# Board_AWS_ESP32_v6.net
KiCad netlist of a schematic drawn in EAGLE
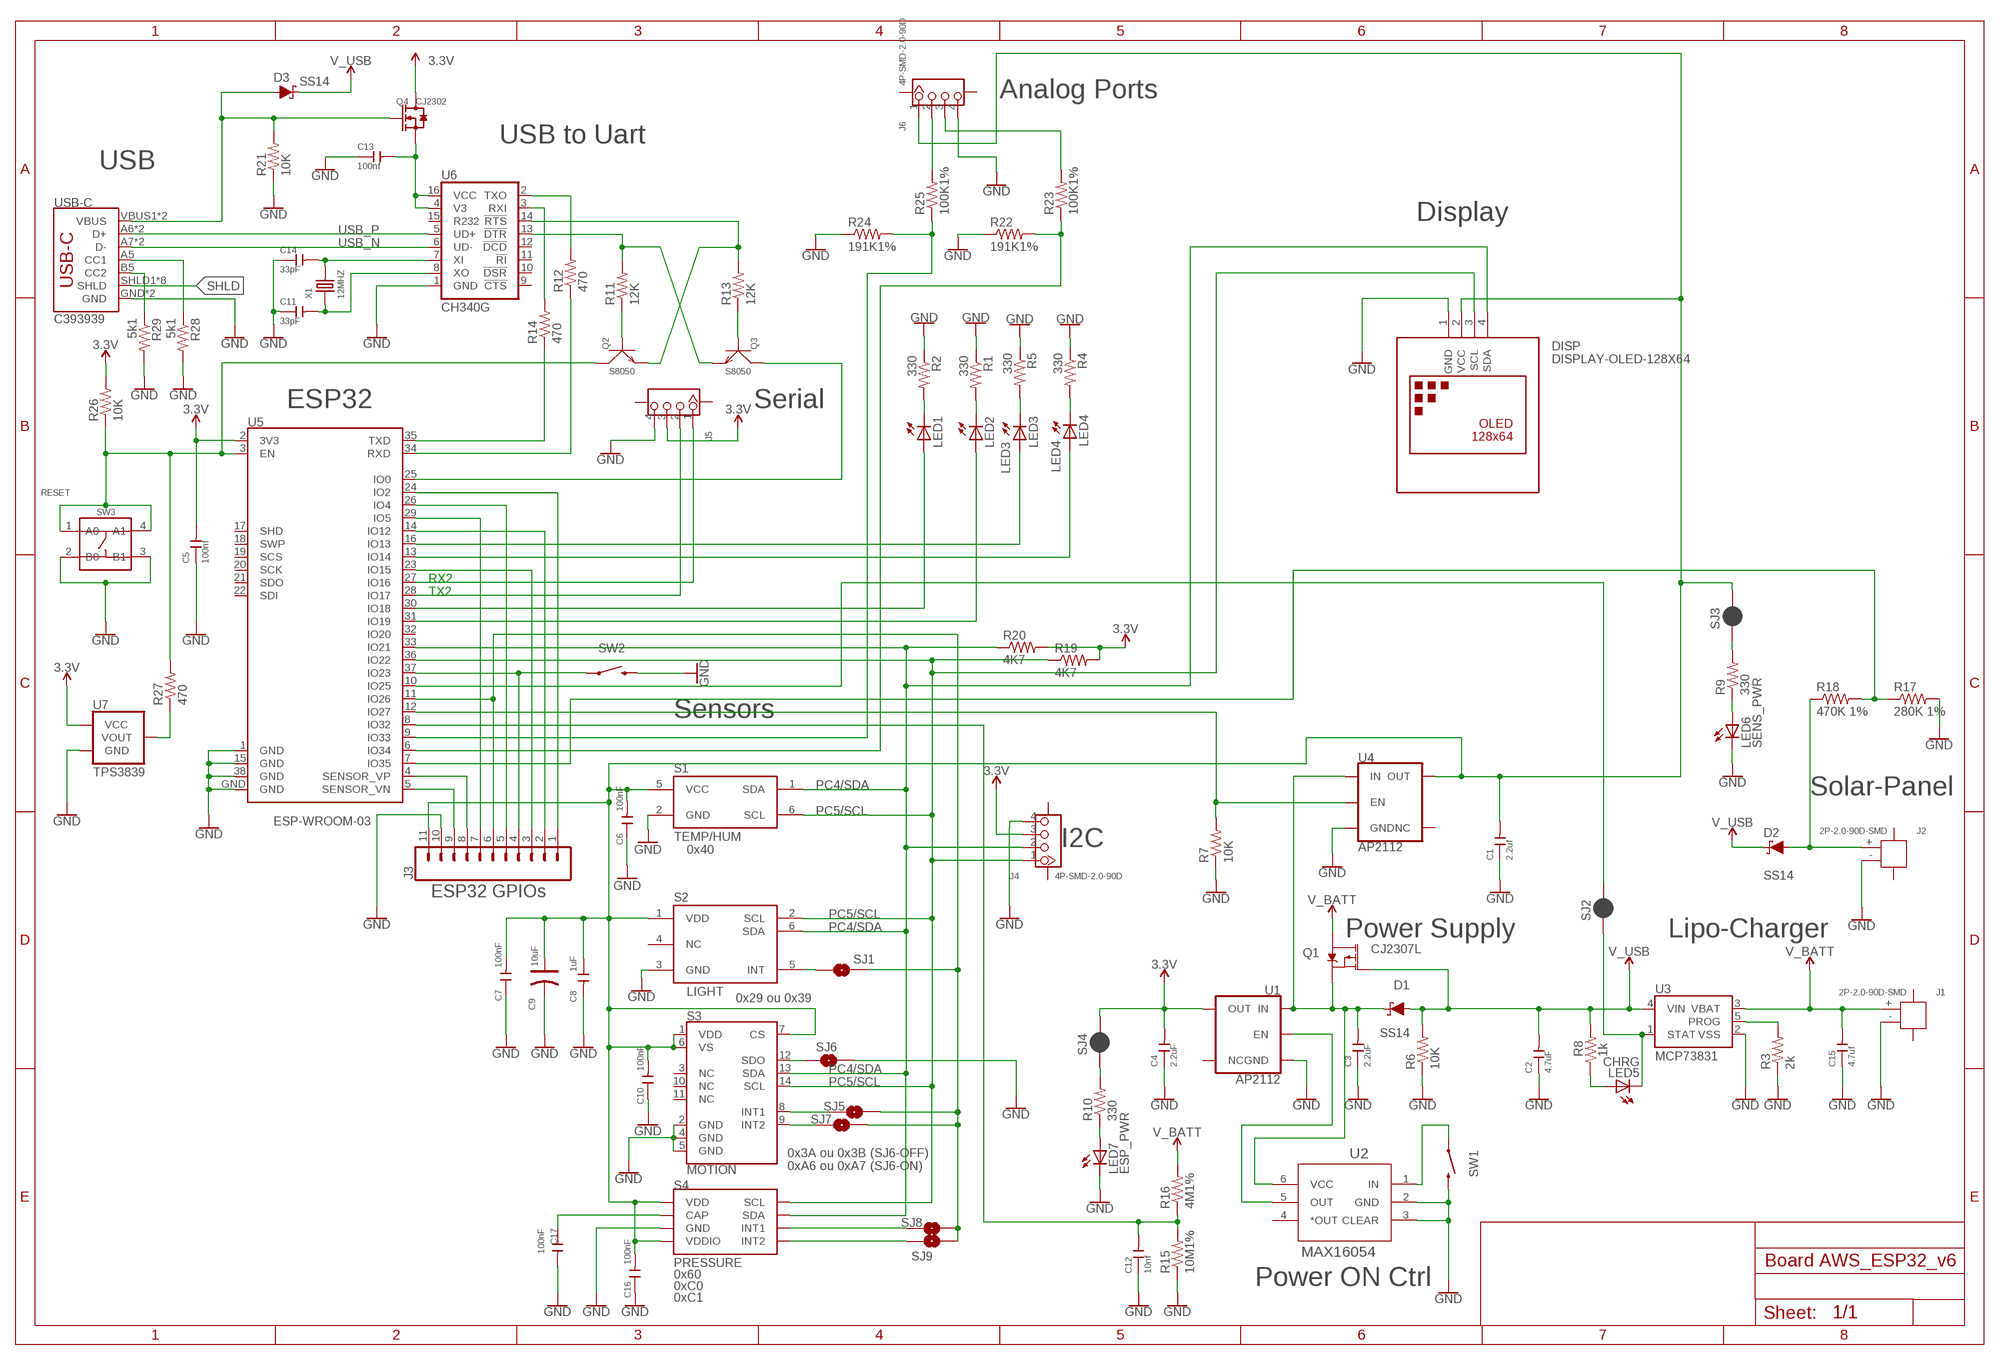
[diagram p0: schematic, sheet 1]

(export (version "E")
  (design (tool "Eeschema 10.0.6"))
  (components
    (comp (ref "C1")
      (value "2.2uf")
      (footprint "eagle-import:C0603")
      (fields (field (name "MPN") "CC0603KRX7R6BB225"))
      (libsource (lib "eagle-import") (part "CERAMIC-2.2UF-10V-10%-X7R(0603)"))
    )
    (comp (ref "C2")
      (value "4.7uF")
      (footprint "eagle-import:C0603")
      (fields (field (name "MPN") "CC0603KRX5R6BB475"))
      (libsource (lib "eagle-import") (part "CERAMIC-4.7UF-10V-10%-X5R(0603)"))
    )
    (comp (ref "C3")
      (value "2.2uF")
      (footprint "eagle-import:C0603")
      (fields (field (name "MPN") "CC0603KRX7R6BB225"))
      (libsource (lib "eagle-import") (part "CERAMIC-2.2UF-10V-10%-X7R(0603)"))
    )
    (comp (ref "C4")
      (value "2.2uF")
      (footprint "eagle-import:C0603")
      (fields (field (name "MPN") "CC0603KRX7R6BB225"))
      (libsource (lib "eagle-import") (part "CERAMIC-2.2UF-10V-10%-X7R(0603)"))
    )
    (comp (ref "C5")
      (value "100nf")
      (footprint "eagle-import:C0603")
      (fields (field (name "MPN") "CC0603KRX7R9BB104"))
      (libsource (lib "eagle-import") (part "CERAMIC-100NF-50V-10%-X7R(0603)"))
    )
    (comp (ref "C6")
      (value "100nF")
      (footprint "eagle-import:C0603")
      (libsource (lib "eagle-import") (part "C-0603"))
    )
    (comp (ref "C7")
      (value "100nF")
      (footprint "eagle-import:C0603")
      (libsource (lib "eagle-import") (part "C-0603"))
    )
    (comp (ref "C8")
      (value "1uF")
      (footprint "eagle-import:C0805")
      (libsource (lib "eagle-import") (part "C-0805"))
    )
    (comp (ref "C9")
      (value "10uF")
      (footprint "eagle-import:AVX-A")
      (libsource (lib "eagle-import") (part "CAP-AVX-A"))
    )
    (comp (ref "C10")
      (value "100nF")
      (footprint "eagle-import:C0603")
      (libsource (lib "eagle-import") (part "C-0603"))
    )
    (comp (ref "C11")
      (value "33pF")
      (footprint "eagle-import:C0603")
      (fields (field (name "MPN") "CC0603JRNPO9BN100"))
      (libsource (lib "eagle-import") (part "CERAMIC-10PF-50V-5%-NPO(0603)"))
    )
    (comp (ref "C12")
      (value "10nf")
      (footprint "eagle-import:C0603")
      (fields (field (name "MPN") "CC0603KRX7R9BB104"))
      (libsource (lib "eagle-import") (part "CERAMIC-100NF-50V-10%-X7R(0603)"))
    )
    (comp (ref "C13")
      (value "100nf")
      (footprint "eagle-import:C0603")
      (fields (field (name "MPN") "CC0603KRX7R9BB104"))
      (libsource (lib "eagle-import") (part "CERAMIC-100NF-50V-10%-X7R(0603)"))
    )
    (comp (ref "C14")
      (value "33pF")
      (footprint "eagle-import:C0603")
      (fields (field (name "MPN") "CC0603JRNPO9BN100"))
      (libsource (lib "eagle-import") (part "CERAMIC-10PF-50V-5%-NPO(0603)"))
    )
    (comp (ref "C15")
      (value "4.7uf")
      (footprint "eagle-import:C0603")
      (fields (field (name "MPN") "CC0603KRX5R6BB475"))
      (libsource (lib "eagle-import") (part "CERAMIC-4.7UF-10V-10%-X5R(0603)"))
    )
    (comp (ref "C16")
      (value "100nF")
      (footprint "eagle-import:C0603")
      (libsource (lib "eagle-import") (part "C-0603"))
    )
    (comp (ref "C17")
      (value "100nF")
      (footprint "eagle-import:C0603")
      (libsource (lib "eagle-import") (part "C-0603"))
    )
    (comp (ref "D1")
      (value "SS14")
      (footprint "eagle-import:SMA-DIODE")
      (libsource (lib "eagle-import") (part "DIODE-SCHOTTKY-SS14"))
    )
    (comp (ref "D2")
      (value "SS14")
      (footprint "eagle-import:SMA-DIODE")
      (libsource (lib "eagle-import") (part "DIODE-SCHOTTKY-SS14"))
    )
    (comp (ref "D3")
      (value "SS14")
      (footprint "eagle-import:SMA-DIODE")
      (libsource (lib "eagle-import") (part "DIODE-SCHOTTKY-SS14"))
    )
    (comp (ref "DISP")
      (value "DISPLAY-OLED-128X64")
      (footprint "eagle-import:DISPLAY-OLED-128X64-I2C")
      (libsource (lib "eagle-import") (part "DISPLAY-OLED-128X64-I2C"))
    )
    (comp (ref "J1")
      (value "2P-2.0-90D-SMD")
      (footprint "eagle-import:HW2-SMD-2.0-90D")
      (libsource (lib "eagle-import") (part "CONN-HEADER-SMD-PH-SIDE-(2P-2.0MM)"))
    )
    (comp (ref "J2")
      (value "2P-2.0-90D-SMD")
      (footprint "eagle-import:HW2-SMD-2.0-90D")
      (libsource (lib "eagle-import") (part "CONN-HEADER-SMD-PH-SIDE-(2P-2.0MM)"))
    )
    (comp (ref "J3")
      (value "CONN_11")
      (footprint "eagle-import:1X11")
      (libsource (lib "eagle-import") (part "CONN_11"))
    )
    (comp (ref "J4")
      (value "4P-SMD-2.0-90D")
      (footprint "eagle-import:HW4-SMD-2.0-90D")
      (libsource (lib "eagle-import") (part "GROVE-CONNECTOR-SMD-90D(4+2P-2.0)"))
    )
    (comp (ref "J5")
      (value "4P-SMD-2.0-90D")
      (footprint "eagle-import:HW4-SMD-2.0-90D")
      (libsource (lib "eagle-import") (part "GROVE-CONNECTOR-SMD-90D(4+2P-2.0)"))
    )
    (comp (ref "J6")
      (value "4P-SMD-2.0-90D")
      (footprint "eagle-import:HW4-SMD-2.0-90D")
      (libsource (lib "eagle-import") (part "GROVE-CONNECTOR-SMD-90D(4+2P-2.0)"))
    )
    (comp (ref "LED1")
      (value "LED1")
      (footprint "eagle-import:LED-0603")
      (libsource (lib "eagle-import") (part "LED0603"))
    )
    (comp (ref "LED2")
      (value "LED2")
      (footprint "eagle-import:LED-0603")
      (libsource (lib "eagle-import") (part "LED0603"))
    )
    (comp (ref "LED3")
      (value "LED3")
      (footprint "eagle-import:LED-0603")
      (libsource (lib "eagle-import") (part "LED0603"))
    )
    (comp (ref "LED4")
      (value "LED4")
      (footprint "eagle-import:LED-0603")
      (libsource (lib "eagle-import") (part "LED0603"))
    )
    (comp (ref "LED5")
      (value "CHRG")
      (footprint "eagle-import:LED-0603")
      (libsource (lib "eagle-import") (part "LED0603"))
    )
    (comp (ref "LED6")
      (value "SENS_PWR")
      (footprint "eagle-import:LED-0603")
      (libsource (lib "eagle-import") (part "LED0603"))
    )
    (comp (ref "LED7")
      (value "ESP_PWR")
      (footprint "eagle-import:LED-0603")
      (libsource (lib "eagle-import") (part "LED0603"))
    )
    (comp (ref "Q1")
      (value "CJ2307L")
      (footprint "eagle-import:SOT23-3")
      (libsource (lib "eagle-import") (part "MOSFET_PCH-DMG2307L"))
    )
    (comp (ref "Q2")
      (value "S8050")
      (footprint "eagle-import:SOT-23")
      (libsource (lib "eagle-import") (part "SMD-TRANSISTORS-NPN-25V-500MW-S8050(SOT-23)"))
    )
    (comp (ref "Q3")
      (value "S8050")
      (footprint "eagle-import:SOT-23")
      (libsource (lib "eagle-import") (part "SMD-TRANSISTORS-NPN-25V-500MW-S8050(SOT-23)"))
    )
    (comp (ref "Q4")
      (value "CJ2302")
      (footprint "eagle-import:SOT-23")
      (libsource (lib "eagle-import") (part "SMD-MOSFET-N-CH-20V-2.1A-CJ2302(SOT-23)"))
    )
    (comp (ref "R1")
      (value "330")
      (footprint "eagle-import:0805")
      (libsource (lib "eagle-import") (part "RESISTOR0805-RES"))
    )
    (comp (ref "R2")
      (value "330")
      (footprint "eagle-import:0805")
      (libsource (lib "eagle-import") (part "RESISTOR0805-RES"))
    )
    (comp (ref "R3")
      (value "2k")
      (footprint "eagle-import:0805")
      (libsource (lib "eagle-import") (part "RESISTOR0805-RES"))
    )
    (comp (ref "R4")
      (value "330")
      (footprint "eagle-import:0805")
      (libsource (lib "eagle-import") (part "RESISTOR0805-RES"))
    )
    (comp (ref "R5")
      (value "330")
      (footprint "eagle-import:0805")
      (libsource (lib "eagle-import") (part "RESISTOR0805-RES"))
    )
    (comp (ref "R6")
      (value "10K")
      (footprint "eagle-import:0805")
      (libsource (lib "eagle-import") (part "RESISTOR0805-RES"))
    )
    (comp (ref "R7")
      (value "10K")
      (footprint "eagle-import:0805")
      (libsource (lib "eagle-import") (part "RESISTOR0805-RES"))
    )
    (comp (ref "R8")
      (value "1k")
      (footprint "eagle-import:0805")
      (libsource (lib "eagle-import") (part "RESISTOR0805-RES"))
    )
    (comp (ref "R9")
      (value "330")
      (footprint "eagle-import:0805")
      (libsource (lib "eagle-import") (part "RESISTOR0805-RES"))
    )
    (comp (ref "R10")
      (value "330")
      (footprint "eagle-import:0805")
      (libsource (lib "eagle-import") (part "RESISTOR0805-RES"))
    )
    (comp (ref "R11")
      (value "12K")
      (footprint "eagle-import:0805")
      (libsource (lib "eagle-import") (part "RESISTOR0805-RES"))
    )
    (comp (ref "R12")
      (value "470")
      (footprint "eagle-import:0805")
      (libsource (lib "eagle-import") (part "RESISTOR0805-RES"))
    )
    (comp (ref "R13")
      (value "12K")
      (footprint "eagle-import:0805")
      (libsource (lib "eagle-import") (part "RESISTOR0805-RES"))
    )
    (comp (ref "R14")
      (value "470")
      (footprint "eagle-import:0805")
      (libsource (lib "eagle-import") (part "RESISTOR0805-RES"))
    )
    (comp (ref "R15")
      (value "10M1%")
      (footprint "eagle-import:0805")
      (libsource (lib "eagle-import") (part "RESISTOR0805-RES"))
    )
    (comp (ref "R16")
      (value "4M1%")
      (footprint "eagle-import:0805")
      (libsource (lib "eagle-import") (part "RESISTOR0805-RES"))
    )
    (comp (ref "R17")
      (value "280K 1%")
      (footprint "eagle-import:0805")
      (libsource (lib "eagle-import") (part "RESISTOR0805-RES"))
    )
    (comp (ref "R18")
      (value "470K 1%")
      (footprint "eagle-import:0805")
      (libsource (lib "eagle-import") (part "RESISTOR0805-RES"))
    )
    (comp (ref "R19")
      (value "4K7")
      (footprint "eagle-import:0805")
      (libsource (lib "eagle-import") (part "RESISTOR0805-RES"))
    )
    (comp (ref "R20")
      (value "4K7")
      (footprint "eagle-import:0805")
      (libsource (lib "eagle-import") (part "RESISTOR0805-RES"))
    )
    (comp (ref "R21")
      (value "10K")
      (footprint "eagle-import:0805")
      (libsource (lib "eagle-import") (part "RESISTOR0805-RES"))
    )
    (comp (ref "R22")
      (value "191K1%")
      (footprint "eagle-import:0805")
      (libsource (lib "eagle-import") (part "RESISTOR0805-RES"))
    )
    (comp (ref "R23")
      (value "100K1%")
      (footprint "eagle-import:0805")
      (libsource (lib "eagle-import") (part "RESISTOR0805-RES"))
    )
    (comp (ref "R24")
      (value "191K1%")
      (footprint "eagle-import:0805")
      (libsource (lib "eagle-import") (part "RESISTOR0805-RES"))
    )
    (comp (ref "R25")
      (value "100K1%")
      (footprint "eagle-import:0805")
      (fields (field (name "SPICEPREFIX") "R"))
      (libsource (lib "eagle-import") (part "RESISTOR0805-RES"))
    )
    (comp (ref "R26")
      (value "10K")
      (footprint "eagle-import:0805")
      (libsource (lib "eagle-import") (part "RESISTOR0805-RES"))
    )
    (comp (ref "R27")
      (value "470")
      (footprint "eagle-import:0805")
      (libsource (lib "eagle-import") (part "RESISTOR0805-RES"))
    )
    (comp (ref "R28")
      (value "5k1")
      (footprint "eagle-import:0805")
      (libsource (lib "eagle-import") (part "RESISTOR0805-RES"))
    )
    (comp (ref "R29")
      (value "5k1")
      (footprint "eagle-import:0805")
      (libsource (lib "eagle-import") (part "RESISTOR0805-RES"))
    )
    (comp (ref "S1")
      (value "TEMP/HUM")
      (footprint "eagle-import:WSON6")
      (libsource (lib "eagle-import") (part "HDC1080"))
    )
    (comp (ref "S2")
      (value "LIGHT")
      (footprint "eagle-import:FN-6")
      (libsource (lib "eagle-import") (part "TSL2571FN"))
    )
    (comp (ref "S3")
      (value "MOTION")
      (footprint "eagle-import:LGA-14")
      (libsource (lib "eagle-import") (part "ADXL345"))
    )
    (comp (ref "S4")
      (value "PRESSURE")
      (footprint "eagle-import:LGA8")
      (libsource (lib "eagle-import") (part "MPL3115A2LGA8"))
    )
    (comp (ref "SJ1")
      (value "IRQ_LIGHT")
      (footprint "eagle-import:SJ_2S-NO")
      (libsource (lib "eagle-import") (part "SOLDERJUMPERNO"))
    )
    (comp (ref "SJ2")
      (value "JUMPER-SMT_2_NC_PASTE_SILK")
      (footprint "eagle-import:SMT-JUMPER_2_NC_PASTE_SILK")
      (libsource (lib "eagle-import") (part "JUMPER-SMT_2_NC_PASTE_SILK"))
    )
    (comp (ref "SJ3")
      (value "JUMPER-SMT_2_NC_PASTE_SILK")
      (footprint "eagle-import:SMT-JUMPER_2_NC_PASTE_SILK")
      (libsource (lib "eagle-import") (part "JUMPER-SMT_2_NC_PASTE_SILK"))
    )
    (comp (ref "SJ4")
      (value "JUMPER-SMT_2_NC_PASTE_SILK")
      (footprint "eagle-import:SMT-JUMPER_2_NC_PASTE_SILK")
      (libsource (lib "eagle-import") (part "JUMPER-SMT_2_NC_PASTE_SILK"))
    )
    (comp (ref "SJ5")
      (value "INT1")
      (footprint "eagle-import:SJ_2S-NO")
      (libsource (lib "eagle-import") (part "SOLDERJUMPERNO"))
    )
    (comp (ref "SJ6")
      (value "ADXL_ADDRESS")
      (footprint "eagle-import:SJ_2S-NO")
      (libsource (lib "eagle-import") (part "SOLDERJUMPERNO"))
    )
    (comp (ref "SJ7")
      (value "INT1")
      (footprint "eagle-import:SJ_2S-NO")
      (libsource (lib "eagle-import") (part "SOLDERJUMPERNO"))
    )
    (comp (ref "SJ8")
      (value "INT1")
      (footprint "eagle-import:SJ_2S-NO")
      (libsource (lib "eagle-import") (part "SOLDERJUMPERNO"))
    )
    (comp (ref "SJ9")
      (value "INT2")
      (footprint "eagle-import:SJ_2S-NO")
      (libsource (lib "eagle-import") (part "SOLDERJUMPERNO"))
    )
    (comp (ref "SW1")
      (value "MOMENTARY-SWITCH-SPST-SMD-6.0X3.5MM")
      (footprint "eagle-import:TACTILE_SWITCH_SMD_6.0X3.5MM")
      (libsource (lib "eagle-import") (part "MOMENTARY-SWITCH-SPST-SMD-6.0X3.5MM"))
    )
    (comp (ref "SW2")
      (value "MOMENTARY-SWITCH-SPST-SMD-6.0X3.5MM")
      (footprint "eagle-import:TACTILE_SWITCH_SMD_6.0X3.5MM")
      (libsource (lib "eagle-import") (part "MOMENTARY-SWITCH-SPST-SMD-6.0X3.5MM"))
    )
    (comp (ref "SW3")
      (value "RESET")
      (footprint "eagle-import:SW4-SMD-6.0X6.0X5.0MM")
      (fields (field (name "MPN") "DTSM-62K-S-V-T/R(SN431)"))
      (libsource (lib "eagle-import") (part "SMD-SWITCH-TACTILE-SPST-NO(4P-D6.0MM)"))
    )
    (comp (ref "U1")
      (value "AP2112")
      (footprint "eagle-import:SOT23-5")
      (libsource (lib "eagle-import") (part "V_REG_AP2112K-3.3V"))
    )
    (comp (ref "U2")
      (value "MAX16054")
      (footprint "eagle-import:SOT23-6")
      (fields (field (name "MF") "Maxim Integrated") (field (name "MPN") "MAX16054AZT+T"))
      (libsource (lib "eagle-import") (part "MAX16054"))
    )
    (comp (ref "U3")
      (value "MCP73831")
      (footprint "eagle-import:SOT23-5")
      (libsource (lib "eagle-import") (part "MCP73831"))
    )
    (comp (ref "U4")
      (value "AP2112")
      (footprint "eagle-import:SOT23-5")
      (libsource (lib "eagle-import") (part "V_REG_AP2112K-3.3V"))
    )
    (comp (ref "U5")
      (value "ESP-WROOM-03")
      (footprint "eagle-import:ESP-WROOM-03")
      (libsource (lib "eagle-import") (part "ESP-WROOM-03"))
    )
    (comp (ref "U6")
      (value "CH340G")
      (footprint "eagle-import:SO016")
      (libsource (lib "eagle-import") (part "CH340GSMD"))
    )
    (comp (ref "U7")
      (value "TPS3839")
      (footprint "eagle-import:SOT23-3")
      (libsource (lib "eagle-import") (part "V_SUPERVISOR"))
    )
    (comp (ref "USB-C")
      (value "C393939")
      (footprint "eagle-import:SPARKFUN-CONNECTORS_USB-C-16P")
      (libsource (lib "eagle-import") (part "SPARKFUN-CONNECTORS_USB_C16PIN"))
    )
    (comp (ref "X1")
      (value "12MHZ")
      (footprint "eagle-import:X2-SMD-5.0X3.2X1.3MM")
      (fields (field (name "MPN") "5032/2P"))
      (libsource (lib "eagle-import") (part "SMD-CRYSTAL-12MHZ-20PF-20PPM-40R(2P-5.0X3.2MM)"))
    )
  )
  (nets
    (net (code "1") (name "/PC4{slash}SDA") (class "Default")
      (node (ref "DISP") (pin "4") (pinfunction "SDA_4") (pintype "bidirectional"))
      (node (ref "J4") (pin "2") (pinfunction "2_2") (pintype "bidirectional"))
      (node (ref "R20") (pin "1") (pinfunction "1_1") (pintype "passive"))
      (node (ref "S1") (pin "1") (pinfunction "SDA_1") (pintype "bidirectional"))
      (node (ref "S2") (pin "6") (pinfunction "SDA_6") (pintype "bidirectional"))
      (node (ref "S3") (pin "13") (pinfunction "SDA_13") (pintype "bidirectional"))
      (node (ref "S4") (pin "7") (pinfunction "SDA_7") (pintype "bidirectional"))
      (node (ref "U5") (pin "33") (pinfunction "IO21_33") (pintype "bidirectional"))
    )
    (net (code "2") (name "/PC5{slash}SCL") (class "Default")
      (node (ref "DISP") (pin "3") (pinfunction "SCL_3") (pintype "bidirectional"))
      (node (ref "J4") (pin "1") (pinfunction "1_1") (pintype "bidirectional"))
      (node (ref "R19") (pin "1") (pinfunction "1_1") (pintype "passive"))
      (node (ref "S1") (pin "6") (pinfunction "SCL_6") (pintype "bidirectional"))
      (node (ref "S2") (pin "2") (pinfunction "SCL_2") (pintype "input"))
      (node (ref "S3") (pin "14") (pinfunction "SCL_14") (pintype "bidirectional"))
      (node (ref "S4") (pin "8") (pinfunction "SCL_8") (pintype "bidirectional"))
      (node (ref "U5") (pin "36") (pinfunction "IO22_36") (pintype "bidirectional"))
    )
    (net (code "3") (name "/USB_N") (class "Default")
      (node (ref "U6") (pin "6") (pinfunction "UD-_6") (pintype "bidirectional"))
      (node (ref "USB-C") (pin "A7") (pinfunction "D-_A7") (pintype "bidirectional"))
      (node (ref "USB-C") (pin "B7") (pinfunction "D-_B7") (pintype "bidirectional"))
    )
    (net (code "4") (name "/USB_P") (class "Default")
      (node (ref "U6") (pin "5") (pinfunction "UD+_5") (pintype "bidirectional"))
      (node (ref "USB-C") (pin "A6") (pinfunction "D+_A6") (pintype "bidirectional"))
      (node (ref "USB-C") (pin "B6") (pinfunction "D+_B6") (pintype "bidirectional"))
    )
    (net (code "5") (name "3.3V") (class "Default")
      (node (ref "C4") (pin "2") (pinfunction "2_2") (pintype "passive"))
      (node (ref "C5") (pin "2") (pinfunction "2_2") (pintype "passive"))
      (node (ref "J4") (pin "3") (pinfunction "3_3") (pintype "bidirectional"))
      (node (ref "J5") (pin "3") (pinfunction "3_3") (pintype "bidirectional"))
      (node (ref "Q4") (pin "3") (pinfunction "D_3") (pintype "passive"))
      (node (ref "R19") (pin "2") (pinfunction "2_2") (pintype "passive"))
      (node (ref "R20") (pin "2") (pinfunction "2_2") (pintype "passive"))
      (node (ref "R26") (pin "2") (pinfunction "2_2") (pintype "passive"))
      (node (ref "SJ4") (pin "2") (pinfunction "2_2") (pintype "passive"))
      (node (ref "U1") (pin "5") (pinfunction "OUT_5") (pintype "passive"))
      (node (ref "U5") (pin "2") (pinfunction "3V3_2") (pintype "bidirectional"))
      (node (ref "U7") (pin "3") (pinfunction "VCC_3") (pintype "input"))
    )
    (net (code "6") (name "GND") (class "Default")
      (node (ref "C1") (pin "1") (pinfunction "1_1") (pintype "passive"))
      (node (ref "C10") (pin "1") (pinfunction "1_1") (pintype "passive"))
      (node (ref "C11") (pin "1") (pinfunction "1_1") (pintype "passive"))
      (node (ref "C12") (pin "1") (pinfunction "1_1") (pintype "passive"))
      (node (ref "C13") (pin "1") (pinfunction "1_1") (pintype "passive"))
      (node (ref "C14") (pin "1") (pinfunction "1_1") (pintype "passive"))
      (node (ref "C15") (pin "1") (pinfunction "1_1") (pintype "passive"))
      (node (ref "C16") (pin "1") (pinfunction "1_1") (pintype "passive"))
      (node (ref "C17") (pin "2") (pinfunction "2_2") (pintype "passive"))
      (node (ref "C2") (pin "1") (pinfunction "1_1") (pintype "passive"))
      (node (ref "C3") (pin "1") (pinfunction "1_1") (pintype "passive"))
      (node (ref "C4") (pin "1") (pinfunction "1_1") (pintype "passive"))
      (node (ref "C5") (pin "1") (pinfunction "1_1") (pintype "passive"))
      (node (ref "C6") (pin "1") (pinfunction "1_1") (pintype "passive"))
      (node (ref "C7") (pin "1") (pinfunction "1_1") (pintype "passive"))
      (node (ref "C8") (pin "2") (pinfunction "2_2") (pintype "passive"))
      (node (ref "C9") (pin "-") (pinfunction "-_-") (pintype "passive"))
      (node (ref "DISP") (pin "1") (pinfunction "GND_1") (pintype "power_in"))
      (node (ref "J1") (pin "-") (pinfunction "2_-") (pintype "bidirectional"))
      (node (ref "J2") (pin "-") (pinfunction "2_-") (pintype "bidirectional"))
      (node (ref "J3") (pin "10") (pinfunction "10_10") (pintype "passive"))
      (node (ref "J4") (pin "4") (pinfunction "4_4") (pintype "bidirectional"))
      (node (ref "J5") (pin "4") (pinfunction "4_4") (pintype "bidirectional"))
      (node (ref "J6") (pin "4") (pinfunction "4_4") (pintype "bidirectional"))
      (node (ref "LED6") (pin "C") (pinfunction "C_C") (pintype "passive"))
      (node (ref "LED7") (pin "C") (pinfunction "C_C") (pintype "passive"))
      (node (ref "R1") (pin "1") (pinfunction "1_1") (pintype "passive"))
      (node (ref "R15") (pin "1") (pinfunction "1_1") (pintype "passive"))
      (node (ref "R17") (pin "2") (pinfunction "2_2") (pintype "passive"))
      (node (ref "R2") (pin "1") (pinfunction "1_1") (pintype "passive"))
      (node (ref "R21") (pin "1") (pinfunction "1_1") (pintype "passive"))
      (node (ref "R22") (pin "1") (pinfunction "1_1") (pintype "passive"))
      (node (ref "R24") (pin "1") (pinfunction "1_1") (pintype "passive"))
      (node (ref "R28") (pin "2") (pinfunction "2_2") (pintype "passive"))
      (node (ref "R29") (pin "2") (pinfunction "2_2") (pintype "passive"))
      (node (ref "R3") (pin "1") (pinfunction "1_1") (pintype "passive"))
      (node (ref "R4") (pin "1") (pinfunction "1_1") (pintype "passive"))
      (node (ref "R5") (pin "1") (pinfunction "1_1") (pintype "passive"))
      (node (ref "R6") (pin "1") (pinfunction "1_1") (pintype "passive"))
      (node (ref "R7") (pin "1") (pinfunction "1_1") (pintype "passive"))
      (node (ref "S1") (pin "2") (pinfunction "GND_2") (pintype "power_in"))
      (node (ref "S2") (pin "3") (pinfunction "GND_3") (pintype "power_in"))
      (node (ref "S3") (pin "2") (pinfunction "GND_2") (pintype "bidirectional"))
      (node (ref "S3") (pin "4") (pinfunction "GND_4") (pintype "bidirectional"))
      (node (ref "S3") (pin "5") (pinfunction "GND_5") (pintype "bidirectional"))
      (node (ref "S4") (pin "3") (pinfunction "GND_3") (pintype "power_in"))
      (node (ref "SJ6") (pin "2") (pinfunction "2_2") (pintype "passive"))
      (node (ref "SW1") (pin "2") (pinfunction "2_2") (pintype "passive"))
      (node (ref "SW2") (pin "2") (pinfunction "2_2") (pintype "passive"))
      (node (ref "SW3") (pin "2") (pinfunction "B0_2") (pintype "bidirectional"))
      (node (ref "SW3") (pin "3") (pinfunction "B1_3") (pintype "bidirectional"))
      (node (ref "U1") (pin "2") (pinfunction "GND_2") (pintype "input"))
      (node (ref "U2") (pin "2") (pinfunction "GND_2") (pintype "power_in"))
      (node (ref "U2") (pin "3") (pinfunction "CLEAR_3") (pintype "input"))
      (node (ref "U3") (pin "2") (pinfunction "VSS_2") (pintype "power_in"))
      (node (ref "U4") (pin "2") (pinfunction "GND_2") (pintype "input"))
      (node (ref "U5") (pin "1") (pinfunction "GND_1") (pintype "bidirectional"))
      (node (ref "U5") (pin "15") (pinfunction "GND_15") (pintype "bidirectional"))
      (node (ref "U5") (pin "38") (pinfunction "GND_38") (pintype "bidirectional"))
      (node (ref "U5") (pin "GND") (pinfunction "GND_GND") (pintype "bidirectional"))
      (node (ref "U6") (pin "1") (pinfunction "GND_1") (pintype "bidirectional"))
      (node (ref "U7") (pin "1") (pinfunction "GND_1") (pintype "input"))
      (node (ref "USB-C") (pin "GND") (pinfunction "GND_GND") (pintype "bidirectional"))
      (node (ref "USB-C") (pin "GND2") (pinfunction "GND_GND2") (pintype "bidirectional"))
    )
    (net (code "7") (name "Net-(DISP-VCC)") (class "Default")
      (node (ref "C1") (pin "2") (pinfunction "2_2") (pintype "passive"))
      (node (ref "C10") (pin "2") (pinfunction "2_2") (pintype "passive"))
      (node (ref "C16") (pin "2") (pinfunction "2_2") (pintype "passive"))
      (node (ref "C6") (pin "2") (pinfunction "2_2") (pintype "passive"))
      (node (ref "C7") (pin "2") (pinfunction "2_2") (pintype "passive"))
      (node (ref "C8") (pin "1") (pinfunction "1_1") (pintype "passive"))
      (node (ref "C9") (pin "+") (pinfunction "+_+") (pintype "passive"))
      (node (ref "DISP") (pin "2") (pinfunction "VCC_2") (pintype "power_in"))
      (node (ref "J3") (pin "11") (pinfunction "11_11") (pintype "passive"))
      (node (ref "J6") (pin "1") (pinfunction "1_1") (pintype "bidirectional"))
      (node (ref "S1") (pin "5") (pinfunction "VCC_5") (pintype "power_in"))
      (node (ref "S2") (pin "1") (pinfunction "VDD_1") (pintype "power_in"))
      (node (ref "S3") (pin "1") (pinfunction "VDD_1") (pintype "bidirectional"))
      (node (ref "S3") (pin "6") (pinfunction "VS_6") (pintype "bidirectional"))
      (node (ref "S3") (pin "7") (pinfunction "CS_7") (pintype "bidirectional"))
      (node (ref "S4") (pin "1") (pinfunction "VDD_1") (pintype "power_in"))
      (node (ref "S4") (pin "4") (pinfunction "VDDIO_4") (pintype "power_in"))
      (node (ref "SJ3") (pin "2") (pinfunction "2_2") (pintype "passive"))
      (node (ref "U4") (pin "5") (pinfunction "OUT_5") (pintype "passive"))
    )
    (net (code "8") (name "Net-(J2-1)") (class "Default")
      (node (ref "D2") (pin "A") (pinfunction "A_A") (pintype "passive"))
      (node (ref "J2") (pin "+") (pinfunction "1_+") (pintype "bidirectional"))
      (node (ref "R18") (pin "1") (pinfunction "1_1") (pintype "passive"))
    )
    (net (code "9") (name "Net-(J6-Pad2)") (class "Default")
      (node (ref "J6") (pin "2") (pinfunction "2_2") (pintype "bidirectional"))
      (node (ref "R25") (pin "2") (pinfunction "2_2") (pintype "passive"))
    )
    (net (code "10") (name "Net-(J6-Pad3)") (class "Default")
      (node (ref "J6") (pin "3") (pinfunction "3_3") (pintype "bidirectional"))
      (node (ref "R23") (pin "2") (pinfunction "2_2") (pintype "passive"))
    )
    (net (code "11") (name "Net-(LED1-PadC)") (class "Default")
      (node (ref "LED1") (pin "C") (pinfunction "C_C") (pintype "passive"))
      (node (ref "R2") (pin "2") (pinfunction "2_2") (pintype "passive"))
    )
    (net (code "12") (name "Net-(LED2-PadC)") (class "Default")
      (node (ref "LED2") (pin "C") (pinfunction "C_C") (pintype "passive"))
      (node (ref "R1") (pin "2") (pinfunction "2_2") (pintype "passive"))
    )
    (net (code "13") (name "Net-(LED3-PadC)") (class "Default")
      (node (ref "LED3") (pin "C") (pinfunction "C_C") (pintype "passive"))
      (node (ref "R5") (pin "2") (pinfunction "2_2") (pintype "passive"))
    )
    (net (code "14") (name "Net-(LED4-PadC)") (class "Default")
      (node (ref "LED4") (pin "C") (pinfunction "C_C") (pintype "passive"))
      (node (ref "R4") (pin "2") (pinfunction "2_2") (pintype "passive"))
    )
    (net (code "15") (name "Net-(LED5-PadA)") (class "Default")
      (node (ref "LED5") (pin "A") (pinfunction "A_A") (pintype "passive"))
      (node (ref "R8") (pin "1") (pinfunction "1_1") (pintype "passive"))
    )
    (net (code "16") (name "Net-(LED6-PadA)") (class "Default")
      (node (ref "LED6") (pin "A") (pinfunction "A_A") (pintype "passive"))
      (node (ref "R9") (pin "1") (pinfunction "1_1") (pintype "passive"))
    )
    (net (code "17") (name "Net-(LED7-PadA)") (class "Default")
      (node (ref "LED7") (pin "A") (pinfunction "A_A") (pintype "passive"))
      (node (ref "R10") (pin "1") (pinfunction "1_1") (pintype "passive"))
    )
    (net (code "18") (name "Net-(Q1-S)") (class "Default")
      (node (ref "C3") (pin "2") (pinfunction "2_2") (pintype "passive"))
      (node (ref "D1") (pin "C") (pinfunction "C_C") (pintype "passive"))
      (node (ref "Q1") (pin "2") (pinfunction "S_2") (pintype "bidirectional"))
      (node (ref "U1") (pin "1") (pinfunction "IN_1") (pintype "input"))
      (node (ref "U2") (pin "6") (pinfunction "VCC_6") (pintype "power_in"))
      (node (ref "U4") (pin "1") (pinfunction "IN_1") (pintype "input"))
    )
    (net (code "19") (name "Net-(Q2-B)") (class "Default")
      (node (ref "Q2") (pin "1") (pinfunction "B_1") (pintype "passive"))
      (node (ref "R11") (pin "1") (pinfunction "1_1") (pintype "passive"))
    )
    (net (code "20") (name "Net-(Q2-C)") (class "Default")
      (node (ref "Q2") (pin "3") (pinfunction "C_3") (pintype "passive"))
      (node (ref "R26") (pin "1") (pinfunction "1_1") (pintype "passive"))
      (node (ref "R27") (pin "2") (pinfunction "2_2") (pintype "passive"))
      (node (ref "SW3") (pin "1") (pinfunction "A0_1") (pintype "bidirectional"))
      (node (ref "SW3") (pin "4") (pinfunction "A1_4") (pintype "bidirectional"))
      (node (ref "U5") (pin "3") (pinfunction "EN_3") (pintype "bidirectional"))
    )
    (net (code "21") (name "Net-(Q2-E)") (class "Default")
      (node (ref "Q2") (pin "2") (pinfunction "E_2") (pintype "passive"))
      (node (ref "R13") (pin "2") (pinfunction "2_2") (pintype "passive"))
      (node (ref "U6") (pin "14") (pinfunction "~{RTS}_14") (pintype "bidirectional"))
    )
    (net (code "22") (name "Net-(Q3-B)") (class "Default")
      (node (ref "Q3") (pin "1") (pinfunction "B_1") (pintype "passive"))
      (node (ref "R13") (pin "1") (pinfunction "1_1") (pintype "passive"))
    )
    (net (code "23") (name "Net-(Q3-C)") (class "Default")
      (node (ref "Q3") (pin "3") (pinfunction "C_3") (pintype "passive"))
      (node (ref "U5") (pin "25") (pinfunction "IO0_25") (pintype "bidirectional"))
    )
    (net (code "24") (name "Net-(Q3-E)") (class "Default")
      (node (ref "Q3") (pin "2") (pinfunction "E_2") (pintype "passive"))
      (node (ref "R11") (pin "2") (pinfunction "2_2") (pintype "passive"))
      (node (ref "U6") (pin "13") (pinfunction "~{DTR}_13") (pintype "bidirectional"))
    )
    (net (code "25") (name "Net-(Q4-G)") (class "Default")
      (node (ref "D3") (pin "A") (pinfunction "A_A") (pintype "passive"))
      (node (ref "Q4") (pin "1") (pinfunction "G_1") (pintype "passive"))
      (node (ref "R21") (pin "2") (pinfunction "2_2") (pintype "passive"))
      (node (ref "USB-C") (pin "VBUS1") (pinfunction "VBUS_VBUS1") (pintype "bidirectional"))
      (node (ref "USB-C") (pin "VBUS2") (pinfunction "VBUS_VBUS2") (pintype "bidirectional"))
    )
    (net (code "26") (name "Net-(Q4-S)") (class "Default")
      (node (ref "C13") (pin "2") (pinfunction "2_2") (pintype "passive"))
      (node (ref "Q4") (pin "2") (pinfunction "S_2") (pintype "passive"))
      (node (ref "U6") (pin "16") (pinfunction "VCC_16") (pintype "bidirectional"))
      (node (ref "U6") (pin "4") (pinfunction "V3_4") (pintype "bidirectional"))
    )
    (net (code "27") (name "Net-(R9-Pad2)") (class "Default")
      (node (ref "R9") (pin "2") (pinfunction "2_2") (pintype "passive"))
      (node (ref "SJ3") (pin "1") (pinfunction "1_1") (pintype "passive"))
    )
    (net (code "28") (name "Net-(R10-Pad2)") (class "Default")
      (node (ref "R10") (pin "2") (pinfunction "2_2") (pintype "passive"))
      (node (ref "SJ4") (pin "1") (pinfunction "1_1") (pintype "passive"))
    )
    (net (code "29") (name "Net-(S2-INT)") (class "Default")
      (node (ref "S2") (pin "5") (pinfunction "INT_5") (pintype "output"))
      (node (ref "SJ1") (pin "1") (pinfunction "1_1") (pintype "passive"))
    )
    (net (code "30") (name "Net-(S3-INT1)") (class "Default")
      (node (ref "S3") (pin "8") (pinfunction "INT1_8") (pintype "bidirectional"))
      (node (ref "SJ5") (pin "1") (pinfunction "1_1") (pintype "passive"))
    )
    (net (code "31") (name "Net-(S3-INT2)") (class "Default")
      (node (ref "S3") (pin "9") (pinfunction "INT2_9") (pintype "bidirectional"))
      (node (ref "SJ7") (pin "1") (pinfunction "1_1") (pintype "passive"))
    )
    (net (code "32") (name "Net-(S3-SDO)") (class "Default")
      (node (ref "S3") (pin "12") (pinfunction "SDO_12") (pintype "bidirectional"))
      (node (ref "SJ6") (pin "1") (pinfunction "1_1") (pintype "passive"))
    )
    (net (code "33") (name "Net-(S4-CAP)") (class "Default")
      (node (ref "C17") (pin "1") (pinfunction "1_1") (pintype "passive"))
      (node (ref "S4") (pin "2") (pinfunction "CAP_2") (pintype "power_in"))
    )
    (net (code "34") (name "Net-(S4-INT1)") (class "Default")
      (node (ref "S4") (pin "6") (pinfunction "INT1_6") (pintype "output"))
      (node (ref "SJ8") (pin "1") (pinfunction "1_1") (pintype "passive"))
    )
    (net (code "35") (name "Net-(S4-INT2)") (class "Default")
      (node (ref "S4") (pin "5") (pinfunction "INT2_5") (pintype "output"))
      (node (ref "SJ9") (pin "1") (pinfunction "1_1") (pintype "passive"))
    )
    (net (code "36") (name "Net-(U1-EN)") (class "Default")
      (node (ref "U1") (pin "3") (pinfunction "EN_3") (pintype "input"))
      (node (ref "U2") (pin "5") (pinfunction "OUT_5") (pintype "output"))
    )
    (net (code "37") (name "Net-(U2-IN)") (class "Default")
      (node (ref "SW1") (pin "1") (pinfunction "1_1") (pintype "passive"))
      (node (ref "U2") (pin "1") (pinfunction "IN_1") (pintype "input"))
    )
    (net (code "38") (name "Net-(U3-PROG)") (class "Default")
      (node (ref "R3") (pin "2") (pinfunction "2_2") (pintype "passive"))
      (node (ref "U3") (pin "5") (pinfunction "PROG_5") (pintype "input"))
    )
    (net (code "39") (name "Net-(U3-STAT)") (class "Default")
      (node (ref "LED5") (pin "C") (pinfunction "C_C") (pintype "passive"))
      (node (ref "SJ2") (pin "1") (pinfunction "1_1") (pintype "passive"))
      (node (ref "U3") (pin "1") (pinfunction "STAT_1") (pintype "output"))
    )
    (net (code "40") (name "Net-(U4-EN)") (class "Default")
      (node (ref "R7") (pin "2") (pinfunction "2_2") (pintype "passive"))
      (node (ref "U4") (pin "3") (pinfunction "EN_3") (pintype "input"))
      (node (ref "U5") (pin "12") (pinfunction "IO27_12") (pintype "bidirectional"))
    )
    (net (code "41") (name "Net-(U5-IO2)") (class "Default")
      (node (ref "J3") (pin "1") (pinfunction "1_1") (pintype "passive"))
      (node (ref "U5") (pin "24") (pinfunction "IO2_24") (pintype "bidirectional"))
    )
    (net (code "42") (name "Net-(U5-IO4)") (class "Default")
      (node (ref "J3") (pin "5") (pinfunction "5_5") (pintype "passive"))
      (node (ref "U5") (pin "26") (pinfunction "IO4_26") (pintype "bidirectional"))
    )
    (net (code "43") (name "Net-(U5-IO5)") (class "Default")
      (node (ref "J3") (pin "7") (pinfunction "7_7") (pintype "passive"))
      (node (ref "U5") (pin "29") (pinfunction "IO5_29") (pintype "bidirectional"))
    )
    (net (code "44") (name "Net-(U5-IO12)") (class "Default")
      (node (ref "J3") (pin "2") (pinfunction "2_2") (pintype "passive"))
      (node (ref "U5") (pin "14") (pinfunction "IO12_14") (pintype "bidirectional"))
    )
    (net (code "45") (name "Net-(U5-IO13)") (class "Default")
      (node (ref "LED3") (pin "A") (pinfunction "A_A") (pintype "passive"))
      (node (ref "U5") (pin "16") (pinfunction "IO13_16") (pintype "bidirectional"))
    )
    (net (code "46") (name "Net-(U5-IO14)") (class "Default")
      (node (ref "LED4") (pin "A") (pinfunction "A_A") (pintype "passive"))
      (node (ref "U5") (pin "13") (pinfunction "IO14_13") (pintype "bidirectional"))
    )
    (net (code "47") (name "Net-(U5-IO15)") (class "Default")
      (node (ref "J3") (pin "3") (pinfunction "3_3") (pintype "passive"))
      (node (ref "U5") (pin "23") (pinfunction "IO15_23") (pintype "bidirectional"))
    )
    (net (code "48") (name "Net-(U5-IO16)") (class "Default")
      (node (ref "J5") (pin "1") (pinfunction "1_1") (pintype "bidirectional"))
      (node (ref "U5") (pin "27") (pinfunction "IO16_27") (pintype "bidirectional"))
    )
    (net (code "49") (name "Net-(U5-IO17)") (class "Default")
      (node (ref "J5") (pin "2") (pinfunction "2_2") (pintype "bidirectional"))
      (node (ref "U5") (pin "28") (pinfunction "IO17_28") (pintype "bidirectional"))
    )
    (net (code "50") (name "Net-(U5-IO18)") (class "Default")
      (node (ref "LED1") (pin "A") (pinfunction "A_A") (pintype "passive"))
      (node (ref "U5") (pin "30") (pinfunction "IO18_30") (pintype "bidirectional"))
    )
    (net (code "51") (name "Net-(U5-IO19)") (class "Default")
      (node (ref "LED2") (pin "A") (pinfunction "A_A") (pintype "passive"))
      (node (ref "U5") (pin "31") (pinfunction "IO19_31") (pintype "bidirectional"))
    )
    (net (code "52") (name "Net-(U5-IO23)") (class "Default")
      (node (ref "J3") (pin "4") (pinfunction "4_4") (pintype "passive"))
      (node (ref "SW2") (pin "1") (pinfunction "1_1") (pintype "passive"))
      (node (ref "U5") (pin "37") (pinfunction "IO23_37") (pintype "bidirectional"))
    )
    (net (code "53") (name "Net-(U5-IO25)") (class "Default")
      (node (ref "SJ2") (pin "2") (pinfunction "2_2") (pintype "passive"))
      (node (ref "U5") (pin "10") (pinfunction "IO25_10") (pintype "bidirectional"))
    )
    (net (code "54") (name "Net-(U5-IO26)") (class "Default")
      (node (ref "J3") (pin "6") (pinfunction "6_6") (pintype "passive"))
      (node (ref "SJ1") (pin "2") (pinfunction "2_2") (pintype "passive"))
      (node (ref "SJ5") (pin "2") (pinfunction "2_2") (pintype "passive"))
      (node (ref "SJ7") (pin "2") (pinfunction "2_2") (pintype "passive"))
      (node (ref "SJ8") (pin "2") (pinfunction "2_2") (pintype "passive"))
      (node (ref "SJ9") (pin "2") (pinfunction "2_2") (pintype "passive"))
      (node (ref "U5") (pin "11") (pinfunction "IO26_11") (pintype "bidirectional"))
    )
    (net (code "55") (name "Net-(U5-IO32)") (class "Default")
      (node (ref "C12") (pin "2") (pinfunction "2_2") (pintype "passive"))
      (node (ref "R15") (pin "2") (pinfunction "2_2") (pintype "passive"))
      (node (ref "R16") (pin "1") (pinfunction "1_1") (pintype "passive"))
      (node (ref "U5") (pin "8") (pinfunction "IO32_8") (pintype "bidirectional"))
    )
    (net (code "56") (name "Net-(U5-IO33)") (class "Default")
      (node (ref "R24") (pin "2") (pinfunction "2_2") (pintype "passive"))
      (node (ref "R25") (pin "1") (pinfunction "1_1") (pintype "passive"))
      (node (ref "U5") (pin "9") (pinfunction "IO33_9") (pintype "bidirectional"))
    )
    (net (code "57") (name "Net-(U5-IO34)") (class "Default")
      (node (ref "R22") (pin "2") (pinfunction "2_2") (pintype "passive"))
      (node (ref "R23") (pin "1") (pinfunction "1_1") (pintype "passive"))
      (node (ref "U5") (pin "6") (pinfunction "IO34_6") (pintype "bidirectional"))
    )
    (net (code "58") (name "Net-(U5-IO35)") (class "Default")
      (node (ref "R17") (pin "1") (pinfunction "1_1") (pintype "passive"))
      (node (ref "R18") (pin "2") (pinfunction "2_2") (pintype "passive"))
      (node (ref "U5") (pin "7") (pinfunction "IO35_7") (pintype "bidirectional"))
    )
    (net (code "59") (name "Net-(U5-RXD)") (class "Default")
      (node (ref "R12") (pin "1") (pinfunction "1_1") (pintype "passive"))
      (node (ref "U5") (pin "34") (pinfunction "RXD_34") (pintype "bidirectional"))
    )
    (net (code "60") (name "Net-(U5-SENSOR_VN)") (class "Default")
      (node (ref "J3") (pin "9") (pinfunction "9_9") (pintype "passive"))
      (node (ref "U5") (pin "5") (pinfunction "SENSOR_VN_5") (pintype "bidirectional"))
    )
    (net (code "61") (name "Net-(U5-SENSOR_VP)") (class "Default")
      (node (ref "J3") (pin "8") (pinfunction "8_8") (pintype "passive"))
      (node (ref "U5") (pin "4") (pinfunction "SENSOR_VP_4") (pintype "bidirectional"))
    )
    (net (code "62") (name "Net-(U5-TXD)") (class "Default")
      (node (ref "R14") (pin "1") (pinfunction "1_1") (pintype "passive"))
      (node (ref "U5") (pin "35") (pinfunction "TXD_35") (pintype "bidirectional"))
    )
    (net (code "63") (name "Net-(U6-RXI)") (class "Default")
      (node (ref "R14") (pin "2") (pinfunction "2_2") (pintype "passive"))
      (node (ref "U6") (pin "3") (pinfunction "RXI_3") (pintype "bidirectional"))
    )
    (net (code "64") (name "Net-(U6-TXO)") (class "Default")
      (node (ref "R12") (pin "2") (pinfunction "2_2") (pintype "passive"))
      (node (ref "U6") (pin "2") (pinfunction "TXO_2") (pintype "bidirectional"))
    )
    (net (code "65") (name "Net-(U6-XI)") (class "Default")
      (node (ref "C14") (pin "2") (pinfunction "2_2") (pintype "passive"))
      (node (ref "U6") (pin "7") (pinfunction "XI_7") (pintype "bidirectional"))
      (node (ref "X1") (pin "2") (pinfunction "2_2") (pintype "passive"))
    )
    (net (code "66") (name "Net-(U6-XO)") (class "Default")
      (node (ref "C11") (pin "2") (pinfunction "2_2") (pintype "passive"))
      (node (ref "U6") (pin "8") (pinfunction "XO_8") (pintype "bidirectional"))
      (node (ref "X1") (pin "1") (pinfunction "1_1") (pintype "passive"))
    )
    (net (code "67") (name "Net-(U7-VOUT)") (class "Default")
      (node (ref "R27") (pin "1") (pinfunction "1_1") (pintype "passive"))
      (node (ref "U7") (pin "2") (pinfunction "VOUT_2") (pintype "output"))
    )
    (net (code "68") (name "Net-(USB-C-CC1)") (class "Default")
      (node (ref "R28") (pin "1") (pinfunction "1_1") (pintype "passive"))
      (node (ref "USB-C") (pin "A5") (pinfunction "CC1_A5") (pintype "bidirectional"))
    )
    (net (code "69") (name "Net-(USB-C-CC2)") (class "Default")
      (node (ref "R29") (pin "1") (pinfunction "1_1") (pintype "passive"))
      (node (ref "USB-C") (pin "B5") (pinfunction "CC2_B5") (pintype "bidirectional"))
    )
    (net (code "70") (name "SHLD") (class "Default")
      (node (ref "USB-C") (pin "SHLD1") (pinfunction "SHLD_SHLD1") (pintype "bidirectional"))
      (node (ref "USB-C") (pin "SHLD2") (pinfunction "SHLD_SHLD2") (pintype "bidirectional"))
      (node (ref "USB-C") (pin "SHLD3") (pinfunction "SHLD_SHLD3") (pintype "bidirectional"))
      (node (ref "USB-C") (pin "SHLD4") (pinfunction "SHLD_SHLD4") (pintype "bidirectional"))
      (node (ref "USB-C") (pin "SHLD5") (pinfunction "SHLD_SHLD5") (pintype "bidirectional"))
      (node (ref "USB-C") (pin "SHLD6") (pinfunction "SHLD_SHLD6") (pintype "bidirectional"))
      (node (ref "USB-C") (pin "SHLD7") (pinfunction "SHLD_SHLD7") (pintype "bidirectional"))
      (node (ref "USB-C") (pin "SHLD8") (pinfunction "SHLD_SHLD8") (pintype "bidirectional"))
    )
    (net (code "71") (name "V_BATT") (class "Default")
      (node (ref "C15") (pin "2") (pinfunction "2_2") (pintype "passive"))
      (node (ref "J1") (pin "+") (pinfunction "1_+") (pintype "bidirectional"))
      (node (ref "Q1") (pin "3") (pinfunction "D_3") (pintype "bidirectional"))
      (node (ref "R16") (pin "2") (pinfunction "2_2") (pintype "passive"))
      (node (ref "U3") (pin "3") (pinfunction "VBAT_3") (pintype "power_in"))
    )
    (net (code "72") (name "V_USB") (class "Default")
      (node (ref "C2") (pin "2") (pinfunction "2_2") (pintype "passive"))
      (node (ref "D1") (pin "A") (pinfunction "A_A") (pintype "passive"))
      (node (ref "D2") (pin "C") (pinfunction "C_C") (pintype "passive"))
      (node (ref "D3") (pin "C") (pinfunction "C_C") (pintype "passive"))
      (node (ref "Q1") (pin "1") (pinfunction "G_1") (pintype "bidirectional"))
      (node (ref "R6") (pin "2") (pinfunction "2_2") (pintype "passive"))
      (node (ref "R8") (pin "2") (pinfunction "2_2") (pintype "passive"))
      (node (ref "U3") (pin "4") (pinfunction "VIN_4") (pintype "power_in"))
    )
    (net (code "73") (name "unconnected-(J1-Pad3)") (class "Default")
      (node (ref "J1") (pin "3") (pinfunction "3_3") (pintype "bidirectional"))
    )
    (net (code "74") (name "unconnected-(J1-Pad4)") (class "Default")
      (node (ref "J1") (pin "4") (pinfunction "4_4") (pintype "bidirectional"))
    )
    (net (code "75") (name "unconnected-(J2-Pad3)") (class "Default")
      (node (ref "J2") (pin "3") (pinfunction "3_3") (pintype "bidirectional"))
    )
    (net (code "76") (name "unconnected-(J2-Pad4)") (class "Default")
      (node (ref "J2") (pin "4") (pinfunction "4_4") (pintype "bidirectional"))
    )
    (net (code "77") (name "unconnected-(J4-PadSS1)") (class "Default")
      (node (ref "J4") (pin "SS1") (pinfunction "SS1_SS1") (pintype "bidirectional"))
    )
    (net (code "78") (name "unconnected-(J4-PadSS2)") (class "Default")
      (node (ref "J4") (pin "SS2") (pinfunction "SS2_SS2") (pintype "bidirectional"))
    )
    (net (code "79") (name "unconnected-(J5-PadSS1)") (class "Default")
      (node (ref "J5") (pin "SS1") (pinfunction "SS1_SS1") (pintype "bidirectional"))
    )
    (net (code "80") (name "unconnected-(J5-PadSS2)") (class "Default")
      (node (ref "J5") (pin "SS2") (pinfunction "SS2_SS2") (pintype "bidirectional"))
    )
    (net (code "81") (name "unconnected-(J6-PadSS1)") (class "Default")
      (node (ref "J6") (pin "SS1") (pinfunction "SS1_SS1") (pintype "bidirectional"))
    )
    (net (code "82") (name "unconnected-(J6-PadSS2)") (class "Default")
      (node (ref "J6") (pin "SS2") (pinfunction "SS2_SS2") (pintype "bidirectional"))
    )
    (net (code "83") (name "unconnected-(S2-NC-Pad4)") (class "Default")
      (node (ref "S2") (pin "4") (pinfunction "NC_4") (pintype "no_connect"))
    )
    (net (code "84") (name "unconnected-(S3-NC-Pad3)") (class "Default")
      (node (ref "S3") (pin "3") (pinfunction "NC_3") (pintype "bidirectional"))
    )
    (net (code "85") (name "unconnected-(S3-NC-Pad10)") (class "Default")
      (node (ref "S3") (pin "10") (pinfunction "NC_10") (pintype "bidirectional"))
    )
    (net (code "86") (name "unconnected-(S3-NC-Pad11)") (class "Default")
      (node (ref "S3") (pin "11") (pinfunction "NC_11") (pintype "bidirectional"))
    )
    (net (code "87") (name "unconnected-(U1-NC-Pad4)") (class "Default")
      (node (ref "U1") (pin "4") (pinfunction "NC_4") (pintype "no_connect"))
    )
    (net (code "88") (name "unconnected-(U2-*OUT-Pad4)") (class "Default")
      (node (ref "U2") (pin "4") (pinfunction "*OUT_4") (pintype "output"))
    )
    (net (code "89") (name "unconnected-(U4-NC-Pad4)") (class "Default")
      (node (ref "U4") (pin "4") (pinfunction "NC_4") (pintype "no_connect"))
    )
    (net (code "90") (name "unconnected-(U5-IO20-Pad32)") (class "Default")
      (node (ref "U5") (pin "32") (pinfunction "IO20_32") (pintype "bidirectional"))
    )
    (net (code "91") (name "unconnected-(U5-SCK-Pad20)") (class "Default")
      (node (ref "U5") (pin "20") (pinfunction "SCK_20") (pintype "bidirectional"))
    )
    (net (code "92") (name "unconnected-(U5-SCS-Pad19)") (class "Default")
      (node (ref "U5") (pin "19") (pinfunction "SCS_19") (pintype "bidirectional"))
    )
    (net (code "93") (name "unconnected-(U5-SDI-Pad22)") (class "Default")
      (node (ref "U5") (pin "22") (pinfunction "SDI_22") (pintype "bidirectional"))
    )
    (net (code "94") (name "unconnected-(U5-SDO-Pad21)") (class "Default")
      (node (ref "U5") (pin "21") (pinfunction "SDO_21") (pintype "bidirectional"))
    )
    (net (code "95") (name "unconnected-(U5-SHD-Pad17)") (class "Default")
      (node (ref "U5") (pin "17") (pinfunction "SHD_17") (pintype "bidirectional"))
    )
    (net (code "96") (name "unconnected-(U5-SWP-Pad18)") (class "Default")
      (node (ref "U5") (pin "18") (pinfunction "SWP_18") (pintype "bidirectional"))
    )
    (net (code "97") (name "unconnected-(U6-R232-Pad15)") (class "Default")
      (node (ref "U6") (pin "15") (pinfunction "R232_15") (pintype "bidirectional"))
    )
    (net (code "98") (name "unconnected-(U6-~{CTS}-Pad9)") (class "Default")
      (node (ref "U6") (pin "9") (pinfunction "~{CTS}_9") (pintype "bidirectional"))
    )
    (net (code "99") (name "unconnected-(U6-~{DCD}-Pad12)") (class "Default")
      (node (ref "U6") (pin "12") (pinfunction "~{DCD}_12") (pintype "bidirectional"))
    )
    (net (code "100") (name "unconnected-(U6-~{DSR}-Pad10)") (class "Default")
      (node (ref "U6") (pin "10") (pinfunction "~{DSR}_10") (pintype "bidirectional"))
    )
    (net (code "101") (name "unconnected-(U6-~{RI}-Pad11)") (class "Default")
      (node (ref "U6") (pin "11") (pinfunction "~{RI}_11") (pintype "bidirectional"))
    )
  )
)
